# Modul-WRM1470-r1_0.net
KiCad netlist of a schematic drawn in Altium Designer
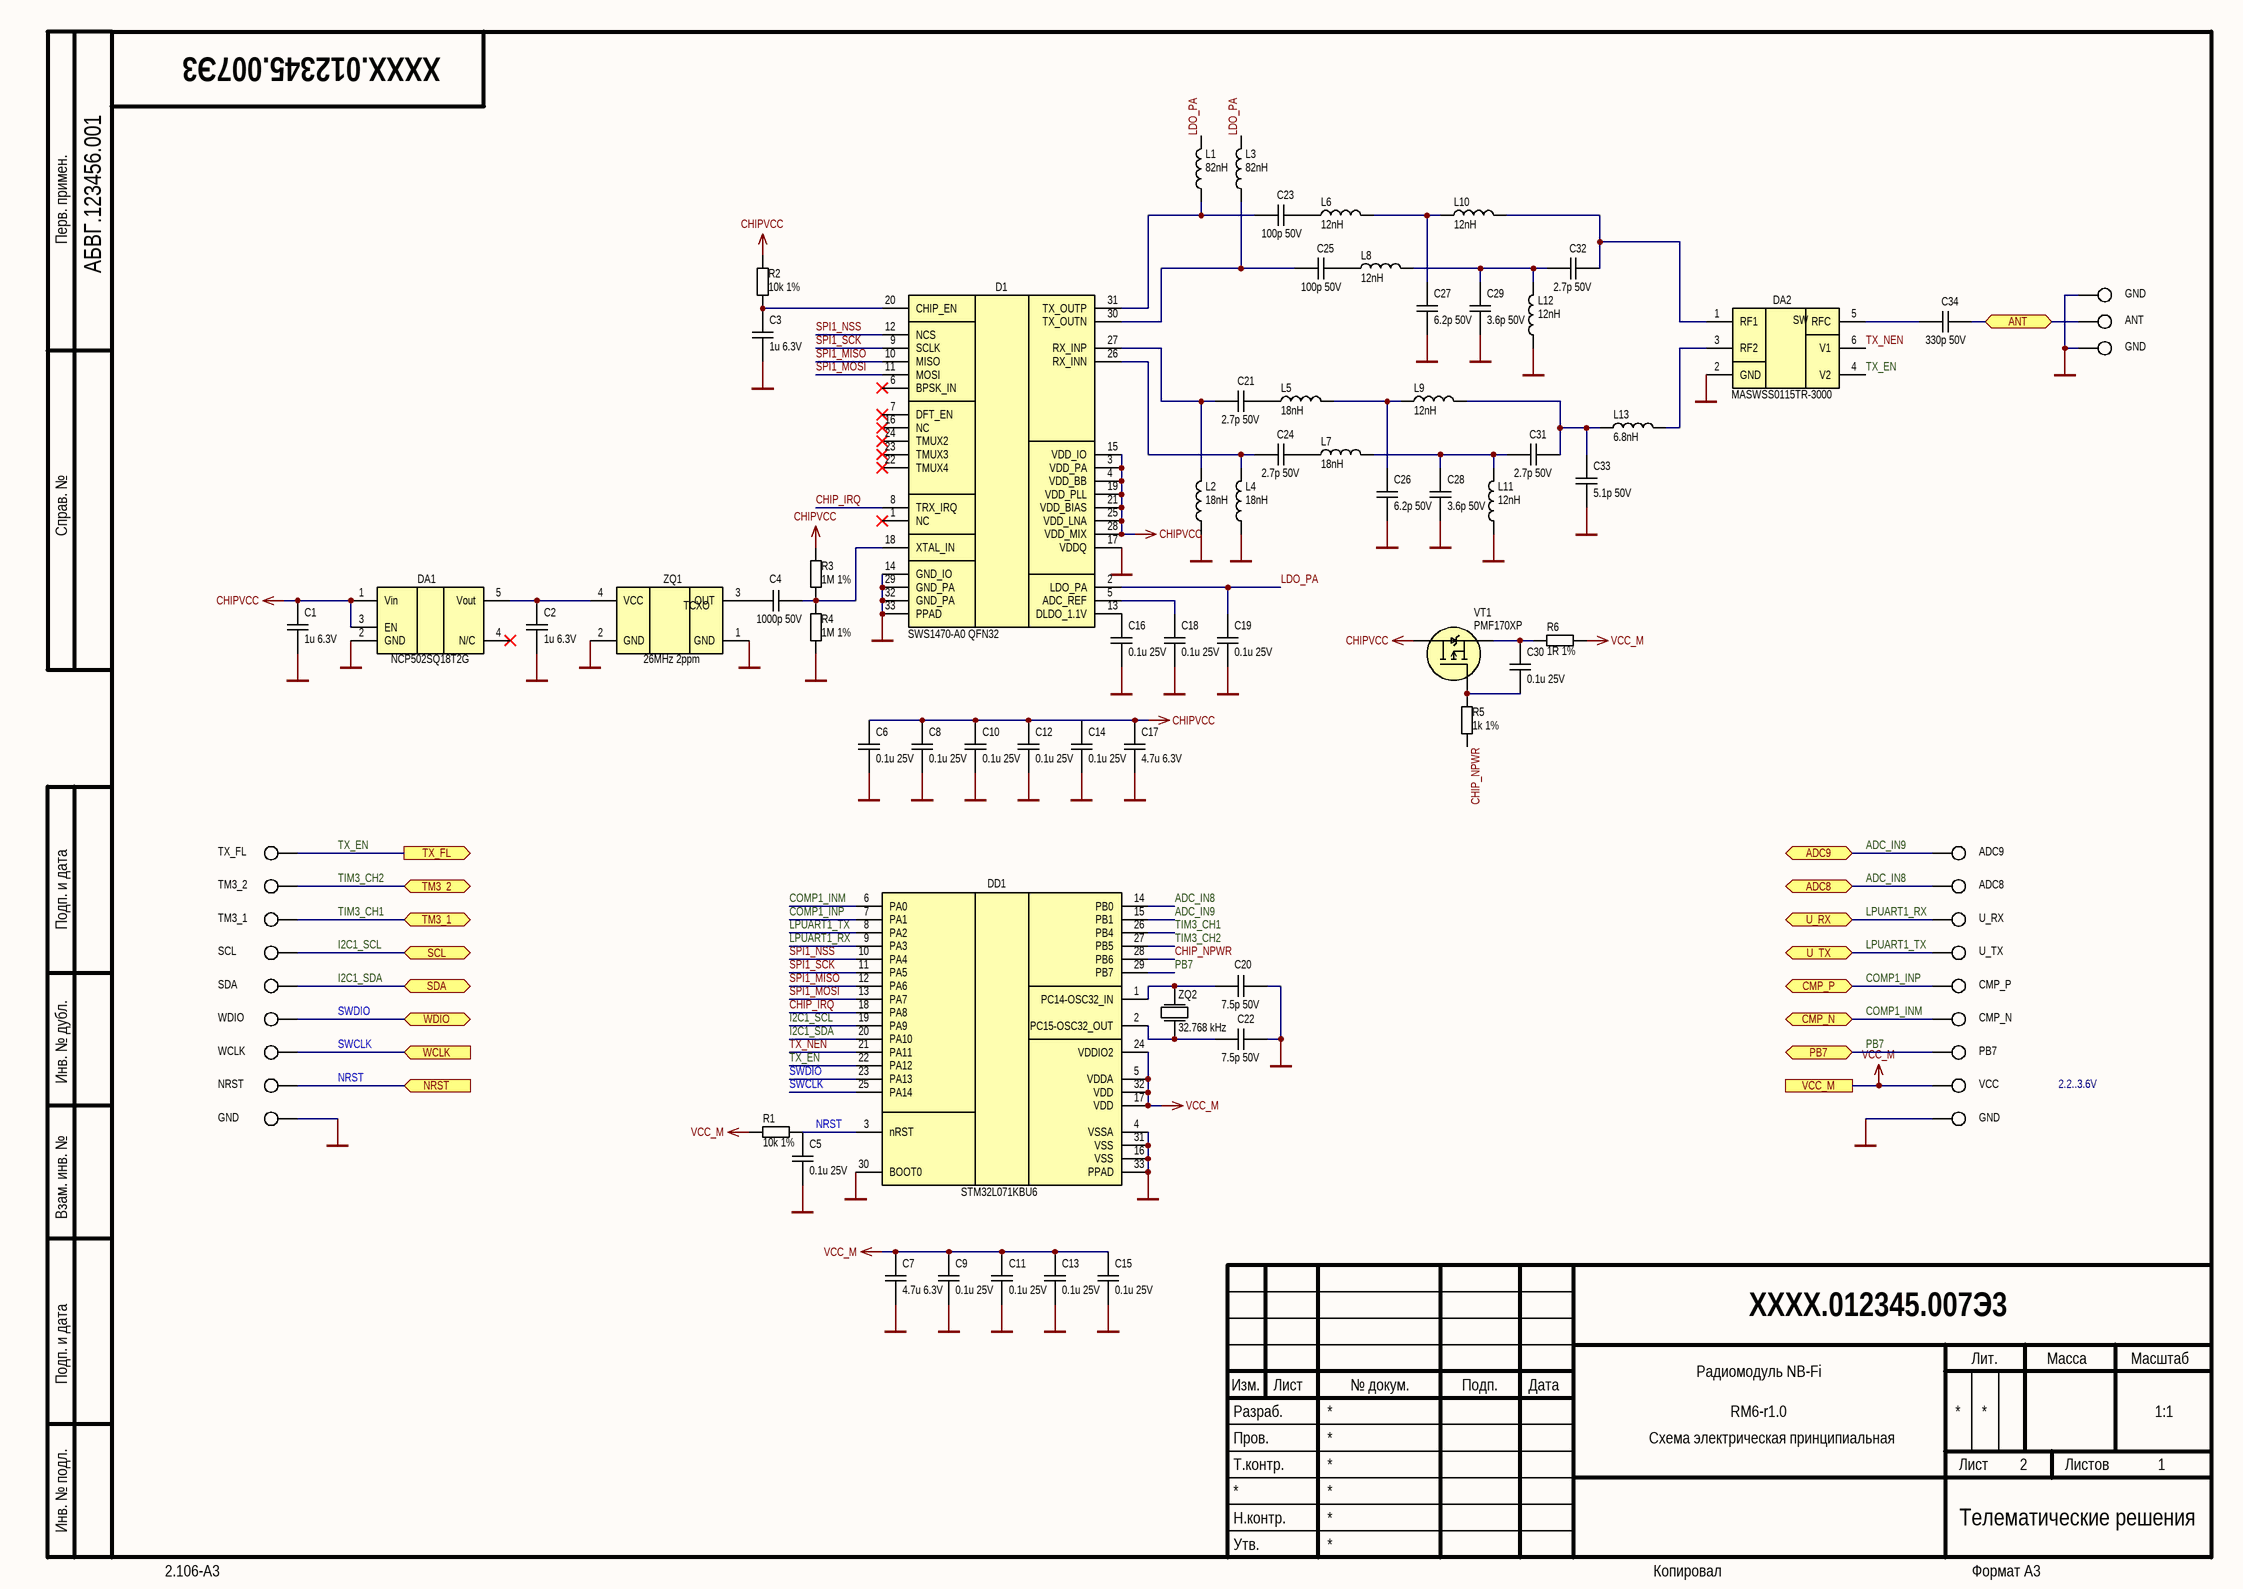
[diagram p0: Modul-WRM1470-r1.0.SchDoc]

(export (version "E")
  (design (tool "Eeschema 10.0.6"))
  (components
    (comp (ref "C1")
      (value "1u 6.3V")
      (footprint "C0402")
      (description "CAP CER 1UF 6.3V X5R 0402")
      (fields (field (name "PARTNUMBER") "CC0402KRX5R5BB105"))
      (libsource (lib "Capacitors") (part "CC0402KRX5R5BB105"))
    )
    (comp (ref "C2")
      (value "1u 6.3V")
      (footprint "C0402")
      (description "CAP CER 1UF 6.3V X5R 0402")
      (fields (field (name "PARTNUMBER") "CC0402KRX5R5BB105"))
      (libsource (lib "Capacitors") (part "CC0402KRX5R5BB105"))
    )
    (comp (ref "C3")
      (value "1u 6.3V")
      (footprint "C0402")
      (description "CAP CER 1UF 6.3V X5R 0402")
      (fields (field (name "PARTNUMBER") "CC0402KRX5R5BB105"))
      (libsource (lib "Capacitors") (part "CC0402KRX5R5BB105"))
    )
    (comp (ref "C4")
      (value "1000p 50V")
      (footprint "C0402")
      (description "CAP CER 1000PF 50V X7R 0402")
      (fields (field (name "PARTNUMBER") "CC0402JRX7R9BB102"))
      (libsource (lib "Capacitors") (part "CC0402JRX7R9BB102"))
    )
    (comp (ref "C5")
      (value "0.1u 25V")
      (footprint "C0402")
      (description "CAP CER 0.1UF 25V X7R 0402")
      (fields (field (name "PARTNUMBER") "CC0402KRX7R8BB104"))
      (libsource (lib "Capacitors") (part "CC0402KRX7R8BB104"))
    )
    (comp (ref "C6")
      (value "0.1u 25V")
      (footprint "C0402")
      (description "CAP CER 0.1UF 25V X7R 0402")
      (fields (field (name "PARTNUMBER") "CC0402KRX7R8BB104"))
      (libsource (lib "Capacitors") (part "CC0402KRX7R8BB104"))
    )
    (comp (ref "C7")
      (value "4.7u 6.3V")
      (footprint "C0402")
      (description "CAP CER 4.7UF 6.3V X5R 0402")
      (fields (field (name "PARTNUMBER") "CC0402KRX5R5BB475"))
      (libsource (lib "Capacitors") (part "CC0402KRX5R5BB475"))
    )
    (comp (ref "C8")
      (value "0.1u 25V")
      (footprint "C0402")
      (description "CAP CER 0.1UF 25V X7R 0402")
      (fields (field (name "PARTNUMBER") "CC0402KRX7R8BB104"))
      (libsource (lib "Capacitors") (part "CC0402KRX7R8BB104"))
    )
    (comp (ref "C9")
      (value "0.1u 25V")
      (footprint "C0402")
      (description "CAP CER 0.1UF 25V X7R 0402")
      (fields (field (name "PARTNUMBER") "CC0402KRX7R8BB104"))
      (libsource (lib "Capacitors") (part "CC0402KRX7R8BB104"))
    )
    (comp (ref "C10")
      (value "0.1u 25V")
      (footprint "C0402")
      (description "CAP CER 0.1UF 25V X7R 0402")
      (fields (field (name "PARTNUMBER") "CC0402KRX7R8BB104"))
      (libsource (lib "Capacitors") (part "CC0402KRX7R8BB104"))
    )
    (comp (ref "C11")
      (value "0.1u 25V")
      (footprint "C0402")
      (description "CAP CER 0.1UF 25V X7R 0402")
      (fields (field (name "PARTNUMBER") "CC0402KRX7R8BB104"))
      (libsource (lib "Capacitors") (part "CC0402KRX7R8BB104"))
    )
    (comp (ref "C12")
      (value "0.1u 25V")
      (footprint "C0402")
      (description "CAP CER 0.1UF 25V X7R 0402")
      (fields (field (name "PARTNUMBER") "CC0402KRX7R8BB104"))
      (libsource (lib "Capacitors") (part "CC0402KRX7R8BB104"))
    )
    (comp (ref "C13")
      (value "0.1u 25V")
      (footprint "C0402")
      (description "CAP CER 0.1UF 25V X7R 0402")
      (fields (field (name "PARTNUMBER") "CC0402KRX7R8BB104"))
      (libsource (lib "Capacitors") (part "CC0402KRX7R8BB104"))
    )
    (comp (ref "C14")
      (value "0.1u 25V")
      (footprint "C0402")
      (description "CAP CER 0.1UF 25V X7R 0402")
      (fields (field (name "PARTNUMBER") "CC0402KRX7R8BB104"))
      (libsource (lib "Capacitors") (part "CC0402KRX7R8BB104"))
    )
    (comp (ref "C15")
      (value "0.1u 25V")
      (footprint "C0402")
      (description "CAP CER 0.1UF 25V X7R 0402")
      (fields (field (name "PARTNUMBER") "CC0402KRX7R8BB104"))
      (libsource (lib "Capacitors") (part "CC0402KRX7R8BB104"))
    )
    (comp (ref "C16")
      (value "0.1u 25V")
      (footprint "C0402")
      (description "CAP CER 0.1UF 25V X7R 0402")
      (fields (field (name "PARTNUMBER") "CC0402KRX7R8BB104"))
      (libsource (lib "Capacitors") (part "CC0402KRX7R8BB104"))
    )
    (comp (ref "C17")
      (value "4.7u 6.3V")
      (footprint "C0402")
      (description "CAP CER 4.7UF 6.3V X5R 0402")
      (fields (field (name "PARTNUMBER") "CC0402KRX5R5BB475"))
      (libsource (lib "Capacitors") (part "CC0402KRX5R5BB475"))
    )
    (comp (ref "C18")
      (value "0.1u 25V")
      (footprint "C0402")
      (description "CAP CER 0.1UF 25V X7R 0402")
      (fields (field (name "PARTNUMBER") "CC0402KRX7R8BB104"))
      (libsource (lib "Capacitors") (part "CC0402KRX7R8BB104"))
    )
    (comp (ref "C19")
      (value "0.1u 25V")
      (footprint "C0402")
      (description "CAP CER 0.1UF 25V X7R 0402")
      (fields (field (name "PARTNUMBER") "CC0402KRX7R8BB104"))
      (libsource (lib "Capacitors") (part "CC0402KRX7R8BB104"))
    )
    (comp (ref "C20")
      (value "7.5p 50V")
      (footprint "C0402")
      (description "CAP CER 7.5PF 50V C0G/NPO 0402")
      (fields (field (name "PARTNUMBER") "CC0402CRNPO9BN7R5"))
      (libsource (lib "Capacitors") (part "CC0402CRNPO9BN7R5"))
    )
    (comp (ref "C21")
      (value "2.7p 50V")
      (footprint "C0402")
      (description "CAP CER 2.7PF 50V C0G/NPO 0402")
      (fields (field (name "PARTNUMBER") "CC0402BRNPO9BN2R7"))
      (libsource (lib "Capacitors") (part "CC0402BRNPO9BN2R7"))
    )
    (comp (ref "C22")
      (value "7.5p 50V")
      (footprint "C0402")
      (description "CAP CER 7.5PF 50V C0G/NPO 0402")
      (fields (field (name "PARTNUMBER") "CC0402CRNPO9BN7R5"))
      (libsource (lib "Capacitors") (part "CC0402CRNPO9BN7R5"))
    )
    (comp (ref "C23")
      (value "100p 50V")
      (footprint "C0402")
      (description "CAP CER 100PF 50V C0G/NPO 0402")
      (fields (field (name "PARTNUMBER") "CC0402JRNPO9BN101"))
      (libsource (lib "Capacitors") (part "CC0402JRNPO9BN101"))
    )
    (comp (ref "C24")
      (value "2.7p 50V")
      (footprint "C0402")
      (description "CAP CER 2.7PF 50V C0G/NPO 0402")
      (fields (field (name "PARTNUMBER") "CC0402BRNPO9BN2R7"))
      (libsource (lib "Capacitors") (part "CC0402BRNPO9BN2R7"))
    )
    (comp (ref "C25")
      (value "100p 50V")
      (footprint "C0402")
      (description "CAP CER 100PF 50V C0G/NPO 0402")
      (fields (field (name "PARTNUMBER") "CC0402JRNPO9BN101"))
      (libsource (lib "Capacitors") (part "CC0402JRNPO9BN101"))
    )
    (comp (ref "C26")
      (value "6.2p 50V")
      (footprint "C0402")
      (description "CAP CER 6.2PF 50V NPO 0402")
      (fields (field (name "PARTNUMBER") "CC0402CRNPO9BN6R2"))
      (libsource (lib "Capacitors") (part "CC0402CRNPO9BN6R2"))
    )
    (comp (ref "C27")
      (value "6.2p 50V")
      (footprint "C0402")
      (description "CAP CER 6.2PF 50V NPO 0402")
      (fields (field (name "PARTNUMBER") "CC0402CRNPO9BN6R2"))
      (libsource (lib "Capacitors") (part "CC0402CRNPO9BN6R2"))
    )
    (comp (ref "C28")
      (value "3.6p 50V")
      (footprint "C0402")
      (description "CAP CER 3.6PF 50V NPO 0402")
      (fields (field (name "PARTNUMBER") "CC0402BRNPO9BN3R6"))
      (libsource (lib "Capacitors") (part "CC0402BRNPO9BN3R6"))
    )
    (comp (ref "C29")
      (value "3.6p 50V")
      (footprint "C0402")
      (description "CAP CER 3.6PF 50V NPO 0402")
      (fields (field (name "PARTNUMBER") "CC0402BRNPO9BN3R6"))
      (libsource (lib "Capacitors") (part "CC0402BRNPO9BN3R6"))
    )
    (comp (ref "C30")
      (value "0.1u 25V")
      (footprint "C0402")
      (description "CAP CER 0.1UF 25V X7R 0402")
      (fields (field (name "PARTNUMBER") "CC0402KRX7R8BB104"))
      (libsource (lib "Capacitors") (part "CC0402KRX7R8BB104"))
    )
    (comp (ref "C31")
      (value "2.7p 50V")
      (footprint "C0402")
      (description "CAP CER 2.7PF 50V C0G/NPO 0402")
      (fields (field (name "PARTNUMBER") "CC0402BRNPO9BN2R7"))
      (libsource (lib "Capacitors") (part "CC0402BRNPO9BN2R7"))
    )
    (comp (ref "C32")
      (value "2.7p 50V")
      (footprint "C0402")
      (description "CAP CER 2.7PF 50V C0G/NPO 0402")
      (fields (field (name "PARTNUMBER") "CC0402BRNPO9BN2R7"))
      (libsource (lib "Capacitors") (part "CC0402BRNPO9BN2R7"))
    )
    (comp (ref "C33")
      (value "5.1p 50V")
      (footprint "C0402")
      (description "CAP CER 5.1PF 50V C0G/NPO 0402")
      (fields (field (name "PARTNUMBER") "CC0402CRNPO9BN5R1"))
      (libsource (lib "Capacitors") (part "CC0402CRNPO9BN5R1"))
    )
    (comp (ref "C34")
      (value "330p 50V")
      (footprint "C0402")
      (description "CAP CER 330PF 50V C0G/NPO 0402")
      (fields (field (name "PARTNUMBER") "CC0402JRNPO9BN331"))
      (libsource (lib "Capacitors") (part "CC0402JRNPO9BN331"))
    )
    (comp (ref "D1")
      (value "SWS1470-A0 QFN32")
      (footprint "QFN32")
      (description "Waviot NB-Fi RF Transceiver QFN32")
      (libsource (lib "Integrated Circuits (ICs)") (part "SWS1470-A0 QFN32"))
    )
    (comp (ref "DA1")
      (value "NCP502SQ18T2G")
      (footprint "SOT323-5")
      (description "IC REG LINEAR 1.8V 80MA SC88A")
      (libsource (lib "Integrated Circuits (ICs)") (part "NCP502SQ18T2G"))
    )
    (comp (ref "DA2")
      (value "MASWSS0115TR-3000")
      (footprint "SOT323-6")
      (description "RF Switch ICs DC-3.0GHz ISO 22dB IL <.3dB @ 2.4GHz")
      (libsource (lib "Integrated Circuits (ICs)") (part "MASWSS0115x"))
    )
    (comp (ref "DD1")
      (value "STM32L071KBU6")
      (footprint "UFQFPN32")
      (description "ARM® Cortex®-M0+ STM32L0 Microcontroller IC 32-Bit 32MHz 128KB (128K x 8) FLASH 32-UFQFPN (5x5)")
      (libsource (lib "Integrated Circuits (ICs)") (part "STM32L071KBU6"))
    )
    (comp (ref "L1")
      (value "82nH")
      (footprint "L0402_LQW")
      (description "FIXED IND 82NH 130MA 2.24 OHM")
      (fields (field (name "PARTNUMBER") "LQW15AN82NG00D"))
      (libsource (lib "Inductors, Coils, Chokes") (part "LQW15AN82NG00D"))
    )
    (comp (ref "L2")
      (value "18nH")
      (footprint "L0402_LQW")
      (description "FIXED IND 18NH 370MA 270 MOHM")
      (fields (field (name "PARTNUMBER") "LQW15AN18NG00D"))
      (libsource (lib "") (part "LQW15AN18NG00D_1"))
    )
    (comp (ref "L3")
      (value "82nH")
      (footprint "L0402_LQW")
      (description "FIXED IND 82NH 130MA 2.24 OHM")
      (fields (field (name "PARTNUMBER") "LQW15AN82NG00D"))
      (libsource (lib "Inductors, Coils, Chokes") (part "LQW15AN82NG00D"))
    )
    (comp (ref "L4")
      (value "18nH")
      (footprint "L0402_LQW")
      (description "FIXED IND 18NH 370MA 270 MOHM")
      (fields (field (name "PARTNUMBER") "LQW15AN18NG00D"))
      (libsource (lib "") (part "LQW15AN18NG00D_1"))
    )
    (comp (ref "L5")
      (value "18nH")
      (footprint "L0402_LQW")
      (description "FIXED IND 18NH 370MA 270 MOHM")
      (fields (field (name "PARTNUMBER") "LQW15AN18NG00D"))
      (libsource (lib "Inductors, Coils, Chokes") (part "LQW15AN18NG00D"))
    )
    (comp (ref "L6")
      (value "12nH")
      (footprint "L0402_LQW")
      (description "FIXED IND 12NH 500MA 140 MOHM")
      (fields (field (name "PARTNUMBER") "LQW15AN12NG00D"))
      (libsource (lib "Inductors, Coils, Chokes") (part "LQW15AN12NG00D"))
    )
    (comp (ref "L7")
      (value "18nH")
      (footprint "L0402_LQW")
      (description "FIXED IND 18NH 370MA 270 MOHM")
      (fields (field (name "PARTNUMBER") "LQW15AN18NG00D"))
      (libsource (lib "Inductors, Coils, Chokes") (part "LQW15AN18NG00D"))
    )
    (comp (ref "L8")
      (value "12nH")
      (footprint "L0402_LQW")
      (description "FIXED IND 12NH 500MA 140 MOHM")
      (fields (field (name "PARTNUMBER") "LQW15AN12NG00D"))
      (libsource (lib "Inductors, Coils, Chokes") (part "LQW15AN12NG00D"))
    )
    (comp (ref "L9")
      (value "12nH")
      (footprint "L0402_LQW")
      (description "FIXED IND 12NH 500MA 140 MOHM")
      (fields (field (name "PARTNUMBER") "LQW15AN12NG00D"))
      (libsource (lib "Inductors, Coils, Chokes") (part "LQW15AN12NG00D"))
    )
    (comp (ref "L10")
      (value "12nH")
      (footprint "L0402_LQW")
      (description "FIXED IND 12NH 500MA 140 MOHM")
      (fields (field (name "PARTNUMBER") "LQW15AN12NG00D"))
      (libsource (lib "Inductors, Coils, Chokes") (part "LQW15AN12NG00D"))
    )
    (comp (ref "L11")
      (value "12nH")
      (footprint "L0402_LQW")
      (description "FIXED IND 12NH 500MA 140 MOHM")
      (fields (field (name "PARTNUMBER") "LQW15AN12NG00D"))
      (libsource (lib "") (part "LQW15AN12NG00D_1"))
    )
    (comp (ref "L12")
      (value "12nH")
      (footprint "L0402_LQW")
      (description "FIXED IND 12NH 500MA 140 MOHM")
      (fields (field (name "PARTNUMBER") "LQW15AN12NG00D"))
      (libsource (lib "") (part "LQW15AN12NG00D_1"))
    )
    (comp (ref "L13")
      (value "6.8nH")
      (footprint "L0402_LQW")
      (description "FIXED IND 6.8NH 700MA 90 MOHM")
      (fields (field (name "PARTNUMBER") "LQW15AN6N8G00D"))
      (libsource (lib "Inductors, Coils, Chokes") (part "LQW15AN6N8G00D"))
    )
    (comp (ref "R1")
      (value "10k 1%")
      (footprint "R0402")
      (description "RES SMD 10K OHM 1% 1/16W 0402")
      (fields (field (name "PARTNUMBER") "RC0402FR-0710KL"))
      (libsource (lib "Resistors") (part "RC0402FR-0710KL"))
    )
    (comp (ref "R2")
      (value "10k 1%")
      (footprint "R0402")
      (description "RES SMD 10K OHM 1% 1/16W 0402")
      (fields (field (name "PARTNUMBER") "RC0402FR-0710KL"))
      (libsource (lib "Resistors") (part "RC0402FR-0710KL"))
    )
    (comp (ref "R3")
      (value "1M 1%")
      (footprint "R0402")
      (description "RES SMD 1M OHM 1% 1/16W 0402")
      (fields (field (name "PARTNUMBER") "RC0402FR-071ML"))
      (libsource (lib "Resistors") (part "RC0402FR-071ML"))
    )
    (comp (ref "R4")
      (value "1M 1%")
      (footprint "R0402")
      (description "RES SMD 1M OHM 1% 1/16W 0402")
      (fields (field (name "PARTNUMBER") "RC0402FR-071ML"))
      (libsource (lib "Resistors") (part "RC0402FR-071ML"))
    )
    (comp (ref "R5")
      (value "1k 1%")
      (footprint "R0402")
      (description "RES SMD 1K OHM 1% 1/16W 0402")
      (fields (field (name "PARTNUMBER") "RC0402FR-071KL"))
      (libsource (lib "Resistors") (part "RC0402FR-071KL"))
    )
    (comp (ref "R6")
      (value "1R 1%")
      (footprint "R0402")
      (description "RES SMD 1 OHM 1% 1/16W 0402")
      (fields (field (name "PARTNUMBER") "RC0402FR-071RL"))
      (libsource (lib "Resistors") (part "RC0402FR-071RL"))
    )
    (comp (ref "VT1")
      (value "PMF170XP")
      (footprint "SOT323")
      (description "MOSFET P-CH 20V 1A SOT323")
      (libsource (lib "Discrete Semiconductor Products") (part "PMF170XP"))
    )
    (comp (ref "X1_1")
      (value "TX_FL")
      (footprint "PAD-d0.6-h1.1-l1.2")
      (libsource (lib "Mount") (part "PIN"))
    )
    (comp (ref "X2_1")
      (value "TM3_2")
      (footprint "PAD-d0.6-h1.1-l1.2")
      (libsource (lib "Mount") (part "PIN"))
    )
    (comp (ref "X3_1")
      (value "TM3_1")
      (footprint "PAD-d0.6-h1.1-l1.2")
      (libsource (lib "Mount") (part "PIN"))
    )
    (comp (ref "X4_1") (value "SCL") (footprint "PAD-d0.6-h1.1-l1.2") (libsource (lib "Mount") (part "PIN")))
    (comp (ref "X5_1") (value "SDA") (footprint "PAD-d0.6-h1.1-l1.2") (libsource (lib "Mount") (part "PIN")))
    (comp (ref "X6_1") (value "WDIO") (footprint "PAD-d0.6-h1.1-l1.2") (libsource (lib "Mount") (part "PIN")))
    (comp (ref "X7_1") (value "WCLK") (footprint "PAD-d0.6-h1.1-l1.2") (libsource (lib "Mount") (part "PIN")))
    (comp (ref "X8_1") (value "NRST") (footprint "PAD-d0.6-h1.1-l1.2") (libsource (lib "Mount") (part "PIN")))
    (comp (ref "X9_1") (value "GND") (footprint "PAD-d0.6-h1.1-l1.2") (libsource (lib "Mount") (part "PIN")))
    (comp (ref "X10_1") (value "GND") (footprint "PAD-d0.6-h1.1-l1.2") (libsource (lib "Mount") (part "PIN")))
    (comp (ref "X11_1") (value "VCC") (footprint "PAD-d0.6-h1.1-l1.2") (libsource (lib "Mount") (part "PIN")))
    (comp (ref "X12_1") (value "PB7") (footprint "PAD-d0.6-h1.1-l1.2") (libsource (lib "Mount") (part "PIN")))
    (comp (ref "X13_1")
      (value "CMP_N")
      (footprint "PAD-d0.6-h1.1-l1.2")
      (libsource (lib "Mount") (part "PIN"))
    )
    (comp (ref "X14_1")
      (value "CMP_P")
      (footprint "PAD-d0.6-h1.1-l1.2")
      (libsource (lib "Mount") (part "PIN"))
    )
    (comp (ref "X15_1")
      (value "U_TX")
      (footprint "PAD-d0.6-h1.1-l1.2")
      (libsource (lib "Mount") (part "PIN"))
    )
    (comp (ref "X16_1")
      (value "U_RX")
      (footprint "PAD-d0.6-h1.1-l1.2")
      (libsource (lib "Mount") (part "PIN"))
    )
    (comp (ref "X17_1")
      (value "ADC8")
      (footprint "PAD-d0.6-h1.1-l1.2")
      (libsource (lib "Mount") (part "PIN"))
    )
    (comp (ref "X18_1")
      (value "ADC9")
      (footprint "PAD-d0.6-h1.1-l1.2")
      (libsource (lib "Mount") (part "PIN"))
    )
    (comp (ref "X19_1") (value "GND") (footprint "PAD-d0.6-h1.1-l1.2") (libsource (lib "Mount") (part "PIN")))
    (comp (ref "X20_1") (value "ANT") (footprint "PAD-d0.6-h1.1-l1.2") (libsource (lib "Mount") (part "PIN")))
    (comp (ref "X21_1") (value "GND") (footprint "PAD-d0.6-h1.1-l1.2") (libsource (lib "Mount") (part "PIN")))
    (comp (ref "ZQ1")
      (value "26MHz 2ppm")
      (footprint "QSMD2.0x1.6x0.7")
      (description "TCXO Oscillator 4-pin")
      (fields (field (name "PARTNUMBER") "NT2016SA-26.000000MHZ-NBG2"))
      (libsource (lib "Crystals, Oscillators, Resonators") (part "NT2016SA-26.000000MHZ-NBG2"))
    )
    (comp (ref "ZQ2")
      (value "32.768 kHz")
      (footprint "QSMD3.2X1.5X0.8")
      (description "Crystals 32.768KHz 12.5pF -40C +85C")
      (fields (field (name "PARTNUMBER") "KX-327NHT 32.768 kHz"))
      (libsource (lib "Crystals, Oscillators, Resonators") (part "KX-327NHT 32.768 kHz"))
    )
  )
  (nets
    (net (code "1") (name "/ADC_IN8") (class "Default")
      (node (ref "DD1") (pin "14") (pinfunction "PB0_14") (pintype "passive"))
      (node (ref "X17_1") (pin "1") (pinfunction "1_1") (pintype "passive"))
    )
    (net (code "2") (name "/ADC_IN9") (class "Default")
      (node (ref "DD1") (pin "15") (pinfunction "PB1_15") (pintype "passive"))
      (node (ref "X18_1") (pin "1") (pinfunction "1_1") (pintype "passive"))
    )
    (net (code "3") (name "/ANT") (class "Default")
      (node (ref "C34") (pin "1") (pinfunction "1_1") (pintype "passive"))
      (node (ref "X20_1") (pin "1") (pinfunction "1_1") (pintype "passive"))
    )
    (net (code "4") (name "/CHIP_IRQ") (class "Default")
      (node (ref "D1") (pin "8") (pinfunction "TRX_IRQ_8") (pintype "passive"))
      (node (ref "DD1") (pin "18") (pinfunction "PA8_18") (pintype "passive"))
    )
    (net (code "5") (name "/CHIP_NPWR") (class "Default")
      (node (ref "DD1") (pin "28") (pinfunction "PB6_28") (pintype "passive"))
      (node (ref "R5") (pin "1") (pinfunction "1_1") (pintype "passive"))
    )
    (net (code "6") (name "/COMP1_INM") (class "Default")
      (node (ref "DD1") (pin "6") (pinfunction "PA0_6") (pintype "passive"))
      (node (ref "X13_1") (pin "1") (pinfunction "1_1") (pintype "passive"))
    )
    (net (code "7") (name "/COMP1_INP") (class "Default")
      (node (ref "DD1") (pin "7") (pinfunction "PA1_7") (pintype "passive"))
      (node (ref "X14_1") (pin "1") (pinfunction "1_1") (pintype "passive"))
    )
    (net (code "8") (name "/I2C1_SCL") (class "Default")
      (node (ref "DD1") (pin "19") (pinfunction "PA9_19") (pintype "passive"))
      (node (ref "X4_1") (pin "1") (pinfunction "1_1") (pintype "passive"))
    )
    (net (code "9") (name "/I2C1_SDA") (class "Default")
      (node (ref "DD1") (pin "20") (pinfunction "PA10_20") (pintype "passive"))
      (node (ref "X5_1") (pin "1") (pinfunction "1_1") (pintype "passive"))
    )
    (net (code "10") (name "/LDO_PA") (class "Default")
      (node (ref "C19") (pin "2") (pinfunction "2_2") (pintype "passive"))
      (node (ref "D1") (pin "2") (pinfunction "LDO_PA_2") (pintype "passive"))
      (node (ref "L1") (pin "2") (pinfunction "2_2") (pintype "passive"))
      (node (ref "L3") (pin "2") (pinfunction "2_2") (pintype "passive"))
    )
    (net (code "11") (name "/LPUART1_RX") (class "Default")
      (node (ref "DD1") (pin "9") (pinfunction "PA3_9") (pintype "passive"))
      (node (ref "X16_1") (pin "1") (pinfunction "1_1") (pintype "passive"))
    )
    (net (code "12") (name "/LPUART1_TX") (class "Default")
      (node (ref "DD1") (pin "8") (pinfunction "PA2_8") (pintype "passive"))
      (node (ref "X15_1") (pin "1") (pinfunction "1_1") (pintype "passive"))
    )
    (net (code "13") (name "/NRST") (class "Default")
      (node (ref "C5") (pin "1") (pinfunction "1_1") (pintype "passive"))
      (node (ref "DD1") (pin "3") (pinfunction "nRST_3") (pintype "passive"))
      (node (ref "R1") (pin "2") (pinfunction "2_2") (pintype "passive"))
      (node (ref "X8_1") (pin "1") (pinfunction "1_1") (pintype "passive"))
    )
    (net (code "14") (name "/PB7") (class "Default")
      (node (ref "DD1") (pin "29") (pinfunction "PB7_29") (pintype "passive"))
      (node (ref "X12_1") (pin "1") (pinfunction "1_1") (pintype "passive"))
    )
    (net (code "15") (name "/SPI1_MISO") (class "Default")
      (node (ref "D1") (pin "10") (pinfunction "MISO_10") (pintype "passive"))
      (node (ref "DD1") (pin "12") (pinfunction "PA6_12") (pintype "passive"))
    )
    (net (code "16") (name "/SPI1_MOSI") (class "Default")
      (node (ref "D1") (pin "11") (pinfunction "MOSI_11") (pintype "passive"))
      (node (ref "DD1") (pin "13") (pinfunction "PA7_13") (pintype "passive"))
    )
    (net (code "17") (name "/SPI1_NSS") (class "Default")
      (node (ref "D1") (pin "12") (pinfunction "NCS_12") (pintype "passive"))
      (node (ref "DD1") (pin "10") (pinfunction "PA4_10") (pintype "passive"))
    )
    (net (code "18") (name "/SPI1_SCK") (class "Default")
      (node (ref "D1") (pin "9") (pinfunction "SCLK_9") (pintype "passive"))
      (node (ref "DD1") (pin "11") (pinfunction "PA5_11") (pintype "passive"))
    )
    (net (code "19") (name "/SWCLK") (class "Default")
      (node (ref "DD1") (pin "25") (pinfunction "PA14_25") (pintype "passive"))
      (node (ref "X7_1") (pin "1") (pinfunction "1_1") (pintype "passive"))
    )
    (net (code "20") (name "/SWDIO") (class "Default")
      (node (ref "DD1") (pin "23") (pinfunction "PA13_23") (pintype "passive"))
      (node (ref "X6_1") (pin "1") (pinfunction "1_1") (pintype "passive"))
    )
    (net (code "21") (name "/TIM3_CH1") (class "Default")
      (node (ref "DD1") (pin "26") (pinfunction "PB4_26") (pintype "passive"))
      (node (ref "X3_1") (pin "1") (pinfunction "1_1") (pintype "passive"))
    )
    (net (code "22") (name "/TIM3_CH2") (class "Default")
      (node (ref "DD1") (pin "27") (pinfunction "PB5_27") (pintype "passive"))
      (node (ref "X2_1") (pin "1") (pinfunction "1_1") (pintype "passive"))
    )
    (net (code "23") (name "/TX_EN") (class "Default")
      (node (ref "DA2") (pin "4") (pinfunction "V2_4") (pintype "passive"))
      (node (ref "DD1") (pin "22") (pinfunction "PA12_22") (pintype "passive"))
      (node (ref "X1_1") (pin "1") (pinfunction "1_1") (pintype "passive"))
    )
    (net (code "24") (name "/TX_NEN") (class "Default")
      (node (ref "DA2") (pin "6") (pinfunction "V1_6") (pintype "passive"))
      (node (ref "DD1") (pin "21") (pinfunction "PA11_21") (pintype "passive"))
    )
    (net (code "25") (name "CHIPVCC") (class "Default")
      (node (ref "C1") (pin "2") (pinfunction "2_2") (pintype "passive"))
      (node (ref "C10") (pin "2") (pinfunction "2_2") (pintype "passive"))
      (node (ref "C12") (pin "2") (pinfunction "2_2") (pintype "passive"))
      (node (ref "C14") (pin "2") (pinfunction "2_2") (pintype "passive"))
      (node (ref "C17") (pin "2") (pinfunction "2_2") (pintype "passive"))
      (node (ref "C6") (pin "2") (pinfunction "2_2") (pintype "passive"))
      (node (ref "C8") (pin "2") (pinfunction "2_2") (pintype "passive"))
      (node (ref "D1") (pin "15") (pinfunction "VDD_IO_15") (pintype "passive"))
      (node (ref "D1") (pin "19") (pinfunction "VDD_PLL_19") (pintype "passive"))
      (node (ref "D1") (pin "21") (pinfunction "VDD_BIAS_21") (pintype "passive"))
      (node (ref "D1") (pin "25") (pinfunction "VDD_LNA_25") (pintype "passive"))
      (node (ref "D1") (pin "28") (pinfunction "VDD_MIX_28") (pintype "passive"))
      (node (ref "D1") (pin "3") (pinfunction "VDD_PA_3") (pintype "passive"))
      (node (ref "D1") (pin "4") (pinfunction "VDD_BB_4") (pintype "passive"))
      (node (ref "DA1") (pin "1") (pinfunction "Vin_1") (pintype "passive"))
      (node (ref "DA1") (pin "3") (pinfunction "EN_3") (pintype "passive"))
      (node (ref "R2") (pin "2") (pinfunction "2_2") (pintype "passive"))
      (node (ref "R3") (pin "2") (pinfunction "2_2") (pintype "passive"))
      (node (ref "VT1") (pin "3") (pinfunction "D_3") (pintype "passive"))
    )
    (net (code "26") (name "GND") (class "Default")
      (node (ref "C1") (pin "1") (pinfunction "1_1") (pintype "passive"))
      (node (ref "C10") (pin "1") (pinfunction "1_1") (pintype "passive"))
      (node (ref "C11") (pin "2") (pinfunction "2_2") (pintype "passive"))
      (node (ref "C12") (pin "1") (pinfunction "1_1") (pintype "passive"))
      (node (ref "C13") (pin "2") (pinfunction "2_2") (pintype "passive"))
      (node (ref "C14") (pin "1") (pinfunction "1_1") (pintype "passive"))
      (node (ref "C15") (pin "2") (pinfunction "2_2") (pintype "passive"))
      (node (ref "C16") (pin "1") (pinfunction "1_1") (pintype "passive"))
      (node (ref "C17") (pin "1") (pinfunction "1_1") (pintype "passive"))
      (node (ref "C18") (pin "1") (pinfunction "1_1") (pintype "passive"))
      (node (ref "C19") (pin "1") (pinfunction "1_1") (pintype "passive"))
      (node (ref "C2") (pin "1") (pinfunction "1_1") (pintype "passive"))
      (node (ref "C20") (pin "2") (pinfunction "2_2") (pintype "passive"))
      (node (ref "C22") (pin "2") (pinfunction "2_2") (pintype "passive"))
      (node (ref "C26") (pin "2") (pinfunction "2_2") (pintype "passive"))
      (node (ref "C27") (pin "2") (pinfunction "2_2") (pintype "passive"))
      (node (ref "C28") (pin "2") (pinfunction "2_2") (pintype "passive"))
      (node (ref "C29") (pin "2") (pinfunction "2_2") (pintype "passive"))
      (node (ref "C3") (pin "1") (pinfunction "1_1") (pintype "passive"))
      (node (ref "C33") (pin "1") (pinfunction "1_1") (pintype "passive"))
      (node (ref "C5") (pin "2") (pinfunction "2_2") (pintype "passive"))
      (node (ref "C6") (pin "1") (pinfunction "1_1") (pintype "passive"))
      (node (ref "C7") (pin "2") (pinfunction "2_2") (pintype "passive"))
      (node (ref "C8") (pin "1") (pinfunction "1_1") (pintype "passive"))
      (node (ref "C9") (pin "2") (pinfunction "2_2") (pintype "passive"))
      (node (ref "D1") (pin "14") (pinfunction "GND_IO_14") (pintype "passive"))
      (node (ref "D1") (pin "17") (pinfunction "VDDQ_17") (pintype "passive"))
      (node (ref "D1") (pin "29") (pinfunction "GND_PA_29") (pintype "passive"))
      (node (ref "D1") (pin "32") (pinfunction "GND_PA_32") (pintype "passive"))
      (node (ref "D1") (pin "33") (pinfunction "PPAD_33") (pintype "passive"))
      (node (ref "DA1") (pin "2") (pinfunction "GND_2") (pintype "passive"))
      (node (ref "DA2") (pin "2") (pinfunction "GND_2") (pintype "passive"))
      (node (ref "DD1") (pin "16") (pinfunction "VSS_16") (pintype "power_in"))
      (node (ref "DD1") (pin "30") (pinfunction "BOOT0_30") (pintype "passive"))
      (node (ref "DD1") (pin "31") (pinfunction "VSS_31") (pintype "power_in"))
      (node (ref "DD1") (pin "33") (pinfunction "PPAD_33") (pintype "power_in"))
      (node (ref "DD1") (pin "4") (pinfunction "VSSA_4") (pintype "power_in"))
      (node (ref "L11") (pin "1") (pinfunction "1_1") (pintype "passive"))
      (node (ref "L12") (pin "1") (pinfunction "1_1") (pintype "passive"))
      (node (ref "L2") (pin "2") (pinfunction "2_2") (pintype "passive"))
      (node (ref "L4") (pin "2") (pinfunction "2_2") (pintype "passive"))
      (node (ref "R4") (pin "1") (pinfunction "1_1") (pintype "passive"))
      (node (ref "X10_1") (pin "1") (pinfunction "1_1") (pintype "passive"))
      (node (ref "X19_1") (pin "1") (pinfunction "1_1") (pintype "passive"))
      (node (ref "X21_1") (pin "1") (pinfunction "1_1") (pintype "passive"))
      (node (ref "X9_1") (pin "1") (pinfunction "1_1") (pintype "passive"))
      (node (ref "ZQ1") (pin "1") (pinfunction "GND_1") (pintype "passive"))
      (node (ref "ZQ1") (pin "2") (pinfunction "GND_2") (pintype "passive"))
    )
    (net (code "27") (name "Net-(C21-Pad2)") (class "Default")
      (node (ref "C21") (pin "2") (pinfunction "2_2") (pintype "passive"))
      (node (ref "L5") (pin "1") (pinfunction "1_1") (pintype "passive"))
    )
    (net (code "28") (name "Net-(C23-Pad2)") (class "Default")
      (node (ref "C23") (pin "2") (pinfunction "2_2") (pintype "passive"))
      (node (ref "L6") (pin "1") (pinfunction "1_1") (pintype "passive"))
    )
    (net (code "29") (name "Net-(C24-Pad2)") (class "Default")
      (node (ref "C24") (pin "2") (pinfunction "2_2") (pintype "passive"))
      (node (ref "L7") (pin "1") (pinfunction "1_1") (pintype "passive"))
    )
    (net (code "30") (name "Net-(C25-Pad2)") (class "Default")
      (node (ref "C25") (pin "2") (pinfunction "2_2") (pintype "passive"))
      (node (ref "L8") (pin "1") (pinfunction "1_1") (pintype "passive"))
    )
    (net (code "31") (name "Net-(C26-Pad1)") (class "Default")
      (node (ref "C26") (pin "1") (pinfunction "1_1") (pintype "passive"))
      (node (ref "L5") (pin "2") (pinfunction "2_2") (pintype "passive"))
      (node (ref "L9") (pin "1") (pinfunction "1_1") (pintype "passive"))
    )
    (net (code "32") (name "Net-(C27-Pad1)") (class "Default")
      (node (ref "C27") (pin "1") (pinfunction "1_1") (pintype "passive"))
      (node (ref "L10") (pin "1") (pinfunction "1_1") (pintype "passive"))
      (node (ref "L6") (pin "2") (pinfunction "2_2") (pintype "passive"))
    )
    (net (code "33") (name "Net-(C28-Pad1)") (class "Default")
      (node (ref "C28") (pin "1") (pinfunction "1_1") (pintype "passive"))
      (node (ref "C31") (pin "1") (pinfunction "1_1") (pintype "passive"))
      (node (ref "L11") (pin "2") (pinfunction "2_2") (pintype "passive"))
      (node (ref "L7") (pin "2") (pinfunction "2_2") (pintype "passive"))
    )
    (net (code "34") (name "Net-(C29-Pad1)") (class "Default")
      (node (ref "C29") (pin "1") (pinfunction "1_1") (pintype "passive"))
      (node (ref "C32") (pin "1") (pinfunction "1_1") (pintype "passive"))
      (node (ref "L12") (pin "2") (pinfunction "2_2") (pintype "passive"))
      (node (ref "L8") (pin "2") (pinfunction "2_2") (pintype "passive"))
    )
    (net (code "35") (name "Net-(C31-Pad2)") (class "Default")
      (node (ref "C31") (pin "2") (pinfunction "2_2") (pintype "passive"))
      (node (ref "C33") (pin "2") (pinfunction "2_2") (pintype "passive"))
      (node (ref "L13") (pin "1") (pinfunction "1_1") (pintype "passive"))
      (node (ref "L9") (pin "2") (pinfunction "2_2") (pintype "passive"))
    )
    (net (code "36") (name "Net-(D1-ADC_REF)") (class "Default")
      (node (ref "C18") (pin "2") (pinfunction "2_2") (pintype "passive"))
      (node (ref "D1") (pin "5") (pinfunction "ADC_REF_5") (pintype "passive"))
    )
    (net (code "37") (name "Net-(D1-CHIP_EN)") (class "Default")
      (node (ref "C3") (pin "2") (pinfunction "2_2") (pintype "passive"))
      (node (ref "D1") (pin "20") (pinfunction "CHIP_EN_20") (pintype "passive"))
      (node (ref "R2") (pin "1") (pinfunction "1_1") (pintype "passive"))
    )
    (net (code "38") (name "Net-(D1-DLDO_1.1V)") (class "Default")
      (node (ref "C16") (pin "2") (pinfunction "2_2") (pintype "passive"))
      (node (ref "D1") (pin "13") (pinfunction "DLDO_1.1V_13") (pintype "passive"))
    )
    (net (code "39") (name "Net-(D1-RX_INN)") (class "Default")
      (node (ref "C24") (pin "1") (pinfunction "1_1") (pintype "passive"))
      (node (ref "D1") (pin "26") (pinfunction "RX_INN_26") (pintype "passive"))
      (node (ref "L4") (pin "1") (pinfunction "1_1") (pintype "passive"))
    )
    (net (code "40") (name "Net-(D1-RX_INP)") (class "Default")
      (node (ref "C21") (pin "1") (pinfunction "1_1") (pintype "passive"))
      (node (ref "D1") (pin "27") (pinfunction "RX_INP_27") (pintype "passive"))
      (node (ref "L2") (pin "1") (pinfunction "1_1") (pintype "passive"))
    )
    (net (code "41") (name "Net-(D1-TX_OUTN)") (class "Default")
      (node (ref "C25") (pin "1") (pinfunction "1_1") (pintype "passive"))
      (node (ref "D1") (pin "30") (pinfunction "TX_OUTN_30") (pintype "passive"))
      (node (ref "L3") (pin "1") (pinfunction "1_1") (pintype "passive"))
    )
    (net (code "42") (name "Net-(D1-TX_OUTP)") (class "Default")
      (node (ref "C23") (pin "1") (pinfunction "1_1") (pintype "passive"))
      (node (ref "D1") (pin "31") (pinfunction "TX_OUTP_31") (pintype "passive"))
      (node (ref "L1") (pin "1") (pinfunction "1_1") (pintype "passive"))
    )
    (net (code "43") (name "Net-(D1-XTAL_IN)") (class "Default")
      (node (ref "C4") (pin "2") (pinfunction "2_2") (pintype "passive"))
      (node (ref "D1") (pin "18") (pinfunction "XTAL_IN_18") (pintype "passive"))
      (node (ref "R3") (pin "1") (pinfunction "1_1") (pintype "passive"))
      (node (ref "R4") (pin "2") (pinfunction "2_2") (pintype "passive"))
    )
    (net (code "44") (name "Net-(DA1-Vout)") (class "Default")
      (node (ref "C2") (pin "2") (pinfunction "2_2") (pintype "passive"))
      (node (ref "DA1") (pin "5") (pinfunction "Vout_5") (pintype "passive"))
      (node (ref "ZQ1") (pin "4") (pinfunction "VCC_4") (pintype "passive"))
    )
    (net (code "45") (name "Net-(DA2-RF1)") (class "Default")
      (node (ref "C32") (pin "2") (pinfunction "2_2") (pintype "passive"))
      (node (ref "DA2") (pin "1") (pinfunction "RF1_1") (pintype "passive"))
      (node (ref "L10") (pin "2") (pinfunction "2_2") (pintype "passive"))
    )
    (net (code "46") (name "Net-(DA2-RF2)") (class "Default")
      (node (ref "DA2") (pin "3") (pinfunction "RF2_3") (pintype "passive"))
      (node (ref "L13") (pin "2") (pinfunction "2_2") (pintype "passive"))
    )
    (net (code "47") (name "Net-(DA2-RFC)") (class "Default")
      (node (ref "C34") (pin "2") (pinfunction "2_2") (pintype "passive"))
      (node (ref "DA2") (pin "5") (pinfunction "RFC_5") (pintype "passive"))
    )
    (net (code "48") (name "Net-(DD1-PC14-OSC32_IN)") (class "Default")
      (node (ref "C20") (pin "1") (pinfunction "1_1") (pintype "passive"))
      (node (ref "DD1") (pin "1") (pinfunction "PC14-OSC32_IN_1") (pintype "passive"))
      (node (ref "ZQ2") (pin "1") (pinfunction "1_1") (pintype "passive"))
    )
    (net (code "49") (name "Net-(DD1-PC15-OSC32_OUT)") (class "Default")
      (node (ref "C22") (pin "1") (pinfunction "1_1") (pintype "passive"))
      (node (ref "DD1") (pin "2") (pinfunction "PC15-OSC32_OUT_2") (pintype "passive"))
      (node (ref "ZQ2") (pin "3") (pinfunction "3_3") (pintype "passive"))
    )
    (net (code "50") (name "Net-(VT1-G)") (class "Default")
      (node (ref "C30") (pin "1") (pinfunction "1_1") (pintype "passive"))
      (node (ref "R5") (pin "2") (pinfunction "2_2") (pintype "passive"))
      (node (ref "VT1") (pin "1") (pinfunction "G_1") (pintype "passive"))
    )
    (net (code "51") (name "Net-(VT1-S)") (class "Default")
      (node (ref "C30") (pin "2") (pinfunction "2_2") (pintype "passive"))
      (node (ref "R6") (pin "2") (pinfunction "2_2") (pintype "passive"))
      (node (ref "VT1") (pin "2") (pinfunction "S_2") (pintype "passive"))
    )
    (net (code "52") (name "Net-(ZQ1-OUT)") (class "Default")
      (node (ref "C4") (pin "1") (pinfunction "1_1") (pintype "passive"))
      (node (ref "ZQ1") (pin "3") (pinfunction "OUT_3") (pintype "passive"))
    )
    (net (code "53") (name "VCC_M") (class "Default")
      (node (ref "C11") (pin "1") (pinfunction "1_1") (pintype "passive"))
      (node (ref "C13") (pin "1") (pinfunction "1_1") (pintype "passive"))
      (node (ref "C15") (pin "1") (pinfunction "1_1") (pintype "passive"))
      (node (ref "C7") (pin "1") (pinfunction "1_1") (pintype "passive"))
      (node (ref "C9") (pin "1") (pinfunction "1_1") (pintype "passive"))
      (node (ref "DD1") (pin "17") (pinfunction "VDD_17") (pintype "power_in"))
      (node (ref "DD1") (pin "24") (pinfunction "VDDIO2_24") (pintype "power_in"))
      (node (ref "DD1") (pin "32") (pinfunction "VDD_32") (pintype "power_in"))
      (node (ref "DD1") (pin "5") (pinfunction "VDDA_5") (pintype "power_in"))
      (node (ref "R1") (pin "1") (pinfunction "1_1") (pintype "passive"))
      (node (ref "R6") (pin "1") (pinfunction "1_1") (pintype "passive"))
      (node (ref "X11_1") (pin "1") (pinfunction "1_1") (pintype "passive"))
    )
    (net (code "54") (name "unconnected-(D1-BPSK_IN-Pad6)") (class "Default")
      (node (ref "D1") (pin "6") (pinfunction "BPSK_IN_6") (pintype "passive+no_connect"))
    )
    (net (code "55") (name "unconnected-(D1-DFT_EN-Pad7)") (class "Default")
      (node (ref "D1") (pin "7") (pinfunction "DFT_EN_7") (pintype "passive+no_connect"))
    )
    (net (code "56") (name "unconnected-(D1-NC-Pad1)") (class "Default")
      (node (ref "D1") (pin "1") (pinfunction "NC_1") (pintype "passive+no_connect"))
    )
    (net (code "57") (name "unconnected-(D1-NC-Pad16)") (class "Default")
      (node (ref "D1") (pin "16") (pinfunction "NC_16") (pintype "passive+no_connect"))
    )
    (net (code "58") (name "unconnected-(D1-TMUX2-Pad24)") (class "Default")
      (node (ref "D1") (pin "24") (pinfunction "TMUX2_24") (pintype "passive+no_connect"))
    )
    (net (code "59") (name "unconnected-(D1-TMUX3-Pad23)") (class "Default")
      (node (ref "D1") (pin "23") (pinfunction "TMUX3_23") (pintype "passive+no_connect"))
    )
    (net (code "60") (name "unconnected-(D1-TMUX4-Pad22)") (class "Default")
      (node (ref "D1") (pin "22") (pinfunction "TMUX4_22") (pintype "passive+no_connect"))
    )
    (net (code "61") (name "unconnected-(DA1-N{slash}C-Pad4)") (class "Default")
      (node (ref "DA1") (pin "4") (pinfunction "N/C_4") (pintype "passive+no_connect"))
    )
  )
)
